# PMU.net
KiCad netlist of a schematic drawn in Altium Designer
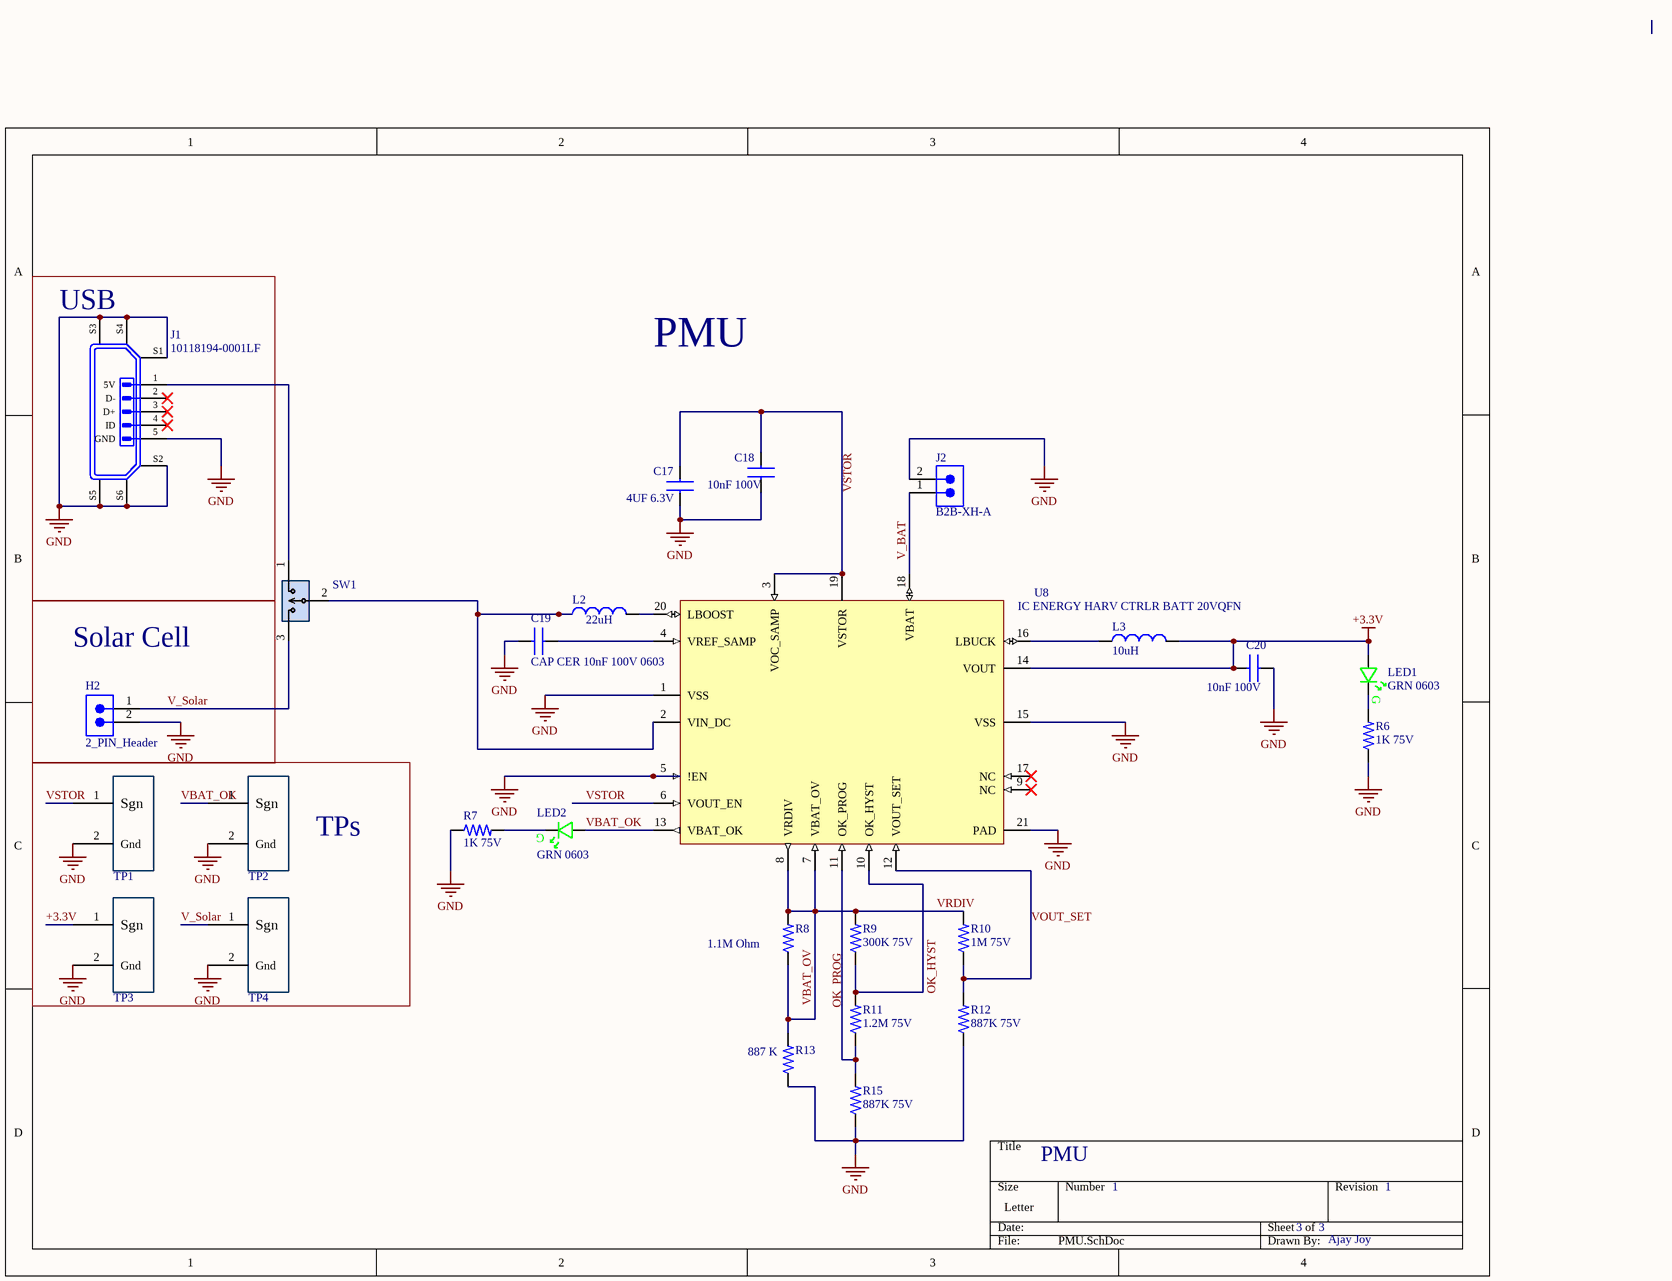
[diagram p0: PMU.SchDoc]

(export (version "E")
  (design (tool "Eeschema 10.0.6"))
  (components
    (comp (ref "C17")
      (value "4UF 6.3V")
      (footprint "CAP_0603_1MM")
      (fields
        (field (name "MANUFACTURER") "Samsung")
        (field (name "MANUFACTURER PART NUMBER") "CL10A105KQ8NNNC")
      )
      (libsource (lib "LPEDT_project_library") (part "CC_1uF_6.3v_0603"))
    )
    (comp (ref "C18")
      (value "10nF 100V")
      (footprint "CAP_0603_1MM")
      (fields
        (field (name "MANUFACTURER") "Murata")
        (field (name "MANUFACTURER PART NUMBER") "GCM188R72A103KA37D")
      )
      (libsource (lib "LPEDT_project_library") (part "GCM188R72A103KA37D"))
    )
    (comp (ref "C19")
      (value "CAP CER 10nF 100V 0603")
      (footprint "CAP_0603_1MM")
      (fields
        (field (name "MANUFACTURER") "Murata")
        (field (name "MANUFACTURER PART NUMBER") "GCM188R72A103KA37D")
      )
      (libsource (lib "LPEDT_project_library") (part "GCM188R72A103KA37D"))
    )
    (comp (ref "C20")
      (value "10nF 100V")
      (footprint "CAP_0603_1MM")
      (fields
        (field (name "MANUFACTURER") "Murata")
        (field (name "MANUFACTURER PART NUMBER") "GCM188R72A103KA37D")
      )
      (libsource (lib "LPEDT_project_library") (part "GCM188R72A103KA37D"))
    )
    (comp (ref "H2")
      (value "2_PIN_Header")
      (footprint "2-PIN_MALE_HEADER_01-IN")
      (description "CONN HEADER VERT 2POS 2.54MM")
      (fields
        (field (name "MANUFACTURER") "Sullins")
        (field (name "MANUFACTURER PART NUMBER") "PRPC002SAAN-RC")
      )
      (libsource (lib "Connectors") (part "PRPC002SAAN-RC"))
    )
    (comp (ref "J1")
      (value "micro-USB")
      (footprint "AMPHENOL_10118194-0001LF")
      (description "10118194-0001LF micro-USB paste-in-pad")
      (fields
        (field (name "MANUFACTURER") "FCI")
        (field (name "MANUFACTURER PART NUMBER") "10118194-0001LF")
        (field (name ".CREATOR") "Kailey Shara")
        (field (name ".SCHCHECKED") "KS")
        (field (name ".PCBCHECKED") "KS")
      )
      (libsource (lib "Connectors") (part "USB-Micro B"))
    )
    (comp (ref "J2")
      (value "B2B-XH-A")
      (footprint "JST_B2B-XH-A(LF)(SN)")
      (description "Board Connector, 2 Contact(s), 1 Row(s), Male, Straight, Solder Terminal,")
      (fields (field (name "MANUFACTURER") "JST"))
      (libsource (lib "LPEDT_project_library") (part "B2B-XH-A"))
    )
    (comp (ref "L2")
      (value "22uH")
      (footprint "IND_0603_1MM")
      (description "22 nH Unshielded Multilayer Inductor 300 mA 400mOhm Max 0603 (1608 Metric)")
      (fields
        (field (name "MANUFACTURER") "Tai Tech")
        (field (name "MANUFACTURER PART NUMBER") "HCI1608F-22NJ-M")
      )
      (libsource (lib "LPEDT_project_library") (part "IND_22nH_0.4OHM_300MA"))
    )
    (comp (ref "L3")
      (value "10uH")
      (footprint "IND_0603_1MM")
      (description "22 nH Unshielded Multilayer Inductor 300 mA 400mOhm Max 0603 (1608 Metric)")
      (fields
        (field (name "MANUFACTURER") "Tai Tech")
        (field (name "MANUFACTURER PART NUMBER") "HCI1608F-22NJ-M")
      )
      (libsource (lib "LPEDT_project_library") (part "IND_22nH_0.4OHM_300MA"))
    )
    (comp (ref "LED1")
      (value "GRN 0603")
      (footprint "LED_0603_GRN_WL-SMCW")
      (description "LED, 0603, GREEN, 430MCD, 520NM")
      (fields
        (field (name "MANUFACTURER") "Wurth Electronics")
        (field (name "MANUFACTURER PART NUMBER") "150060GS75000")
      )
      (libsource (lib "LPEDT_project_library") (part "150060GS75000"))
    )
    (comp (ref "LED2")
      (value "GRN 0603")
      (footprint "LED_0603_GRN_WL-SMCW")
      (description "LED, 0603, GREEN, 430MCD, 520NM")
      (fields
        (field (name "MANUFACTURER") "Wurth Electronics")
        (field (name "MANUFACTURER PART NUMBER") "150060GS75000")
      )
      (libsource (lib "LPEDT_project_library") (part "150060GS75000"))
    )
    (comp (ref "R6")
      (value "1K 75V")
      (footprint "RES_0603_1608X06")
      (fields
        (field (name "MANUFACTURER") "Stackpole Electronics")
        (field (name "MANUFACTURER PART NUMBER") "RMCF0603FT4K70")
        (field (name "TOLERANCE") "1%")
      )
      (libsource (lib "LPEDT_project_library") (part "RMCF0603FT4K70"))
    )
    (comp (ref "R7")
      (value "1K 75V")
      (footprint "RES_0603_1608X06")
      (fields
        (field (name "MANUFACTURER") "Stackpole Electronics")
        (field (name "MANUFACTURER PART NUMBER") "RMCF0603FT4K70")
        (field (name "TOLERANCE") "1%")
      )
      (libsource (lib "LPEDT_project_library") (part "RMCF0603FT4K70"))
    )
    (comp (ref "R8")
      (value "1.1M Ohm")
      (footprint "RES_0603_1608X06")
      (fields
        (field (name "MANUFACTURER") "Stackpole Electronics")
        (field (name "MANUFACTURER PART NUMBER") "RMCF0603FT1M10")
        (field (name "TOLERANCE") "1%")
      )
      (libsource (lib "LPEDT_project_library") (part "RMCF0603FT1M10"))
    )
    (comp (ref "R9")
      (value "300K 75V")
      (footprint "RES_0603_1608X06")
      (fields
        (field (name "MANUFACTURER") "Stackpole Electronics")
        (field (name "MANUFACTURER PART NUMBER") "RMCF0603FT4K70")
        (field (name "TOLERANCE") "1%")
      )
      (libsource (lib "LPEDT_project_library") (part "RMCF0603FT4K70"))
    )
    (comp (ref "R10")
      (value "1M 75V")
      (footprint "RES_0603_1608X06")
      (fields
        (field (name "MANUFACTURER") "Stackpole Electronics")
        (field (name "MANUFACTURER PART NUMBER") "RMCF0603FT4K70")
        (field (name "TOLERANCE") "1%")
      )
      (libsource (lib "LPEDT_project_library") (part "RMCF0603FT4K70"))
    )
    (comp (ref "R11")
      (value "1.2M 75V")
      (footprint "RES_0603_1608X06")
      (fields
        (field (name "MANUFACTURER") "Stackpole Electronics")
        (field (name "MANUFACTURER PART NUMBER") "RMCF0603FT4K70")
        (field (name "TOLERANCE") "1%")
      )
      (libsource (lib "LPEDT_project_library") (part "RMCF0603FT4K70"))
    )
    (comp (ref "R12")
      (value "887K 75V")
      (footprint "RES_0603_1608X06")
      (fields
        (field (name "MANUFACTURER") "Stackpole Electronics")
        (field (name "MANUFACTURER PART NUMBER") "RMCF0603FT4K70")
        (field (name "TOLERANCE") "1%")
      )
      (libsource (lib "LPEDT_project_library") (part "RMCF0603FT4K70"))
    )
    (comp (ref "R13")
      (value "887 K")
      (footprint "RES_0603_1608X06")
      (fields
        (field (name "MANUFACTURER") "Stackpole Electronics")
        (field (name "MANUFACTURER PART NUMBER") "RMCF0603FT1M10")
        (field (name "TOLERANCE") "1%")
      )
      (libsource (lib "LPEDT_project_library") (part "RMCF0603FT1M10"))
    )
    (comp (ref "R15")
      (value "887K 75V")
      (footprint "RES_0603_1608X06")
      (fields
        (field (name "MANUFACTURER") "Stackpole Electronics")
        (field (name "MANUFACTURER PART NUMBER") "RMCF0603FT4K70")
        (field (name "TOLERANCE") "1%")
      )
      (libsource (lib "LPEDT_project_library") (part "RMCF0603FT4K70"))
    )
    (comp (ref "SW1")
      (value "PREC003SAAN-RC")
      (footprint "3_PIN_100mil")
      (description "Connector Header Through Hole 3 position 0.100\" (2.54mm)")
      (fields (field (name "LCSC PART#") "C49257"))
      (libsource (lib "ECEN5730Lib_2023_05_DS") (part "SW_3Pin_100mil_Switch"))
    )
    (comp (ref "TP1")
      (value "TP_Active_Probe")
      (footprint "Active_Probe")
      (description "Active Probe Test Point footprint")
      (libsource (lib "ECEN5730Lib_Manual_2022_07LibPkg_1") (part "TP_Active_Probe"))
    )
    (comp (ref "TP2")
      (value "TP_Active_Probe")
      (footprint "Active_Probe")
      (description "Active Probe Test Point footprint")
      (libsource (lib "ECEN5730Lib_Manual_2022_07LibPkg_1") (part "TP_Active_Probe"))
    )
    (comp (ref "TP3")
      (value "TP_Active_Probe")
      (footprint "Active_Probe")
      (description "Active Probe Test Point footprint")
      (libsource (lib "ECEN5730Lib_Manual_2022_07LibPkg_1") (part "TP_Active_Probe"))
    )
    (comp (ref "TP4")
      (value "TP_Active_Probe")
      (footprint "Active_Probe")
      (description "Active Probe Test Point footprint")
      (libsource (lib "ECEN5730Lib_Manual_2022_07LibPkg_1") (part "TP_Active_Probe"))
    )
    (comp (ref "U8")
      (value "IC ENERGY HARV CTRLR BATT 20VQFN")
      (footprint "20-VQFN_3.3x3.3_BQ25570RGRR")
      (description "Power Supply Support Circuit, Adjustable, 1 Channel, PQCC20")
      (fields
        (field (name "MANUFACTURER") "Texas Instruments")
        (field (name "MANUFACTURER PART NUMBER") "BQ25570RGRR")
      )
      (libsource (lib "LPEDT_project_library") (part "BQ25570RGRR"))
    )
  )
  (nets
    (net (code "1") (name "+3.3V") (class "Default")
      (node (ref "C20") (pin "1") (pinfunction "1_1") (pintype "passive"))
      (node (ref "L3") (pin "2") (pinfunction "2_2") (pintype "passive"))
      (node (ref "LED1") (pin "A") (pinfunction "A_A") (pintype "passive"))
      (node (ref "TP3") (pin "1") (pinfunction "Sgn_1") (pintype "passive"))
      (node (ref "U8") (pin "14") (pinfunction "VOUT_14") (pintype "power_in"))
    )
    (net (code "2") (name "/OK_HYST") (class "Default")
      (node (ref "R11") (pin "2") (pinfunction "2_2") (pintype "passive"))
      (node (ref "R9") (pin "1") (pinfunction "1_1") (pintype "passive"))
      (node (ref "U8") (pin "10") (pinfunction "OK_HYST_10") (pintype "input"))
    )
    (net (code "4") (name "/VBAT_OK") (class "Default")
      (node (ref "LED2") (pin "A") (pinfunction "A_A") (pintype "passive"))
      (node (ref "TP2") (pin "1") (pinfunction "Sgn_1") (pintype "passive"))
      (node (ref "U8") (pin "13") (pinfunction "VBAT_OK_13") (pintype "output"))
    )
    (net (code "5") (name "/VBAT_OV") (class "Default")
      (node (ref "R10") (pin "2") (pinfunction "2_2") (pintype "passive"))
      (node (ref "R13") (pin "2") (pinfunction "2_2") (pintype "passive"))
      (node (ref "R8") (pin "1") (pinfunction "1_1") (pintype "passive"))
      (node (ref "R8") (pin "2") (pinfunction "2_2") (pintype "passive"))
      (node (ref "R9") (pin "2") (pinfunction "2_2") (pintype "passive"))
      (node (ref "U8") (pin "7") (pinfunction "VBAT_OV_7") (pintype "input"))
      (node (ref "U8") (pin "8") (pinfunction "VRDIV_8") (pintype "output"))
    )
    (net (code "6") (name "/VOUT_SET") (class "Default")
      (node (ref "R10") (pin "1") (pinfunction "1_1") (pintype "passive"))
      (node (ref "R12") (pin "2") (pinfunction "2_2") (pintype "passive"))
      (node (ref "U8") (pin "12") (pinfunction "VOUT_SET_12") (pintype "input"))
    )
    (net (code "7") (name "/VSTOR") (class "Default")
      (node (ref "TP1") (pin "1") (pinfunction "Sgn_1") (pintype "passive"))
      (node (ref "U8") (pin "6") (pinfunction "VOUT_EN_6") (pintype "input"))
    )
    (net (code "8") (name "/V_BAT") (class "Default")
      (node (ref "J2") (pin "1") (pinfunction "1_1") (pintype "passive"))
      (node (ref "U8") (pin "18") (pinfunction "VBAT_18") (pintype "bidirectional"))
    )
    (net (code "9") (name "/V_Solar") (class "Default")
      (node (ref "H2") (pin "1") (pinfunction "1_1") (pintype "passive"))
      (node (ref "SW1") (pin "3") (pinfunction "3_3") (pintype "passive"))
      (node (ref "TP4") (pin "1") (pinfunction "Sgn_1") (pintype "passive"))
    )
    (net (code "10") (name "GND") (class "Default")
      (node (ref "C17") (pin "2") (pinfunction "2_2") (pintype "passive"))
      (node (ref "C18") (pin "2") (pinfunction "2_2") (pintype "passive"))
      (node (ref "C19") (pin "1") (pinfunction "1_1") (pintype "passive"))
      (node (ref "C20") (pin "2") (pinfunction "2_2") (pintype "passive"))
      (node (ref "H2") (pin "2") (pinfunction "2_2") (pintype "passive"))
      (node (ref "J1") (pin "5") (pinfunction "GND_5") (pintype "power_in"))
      (node (ref "J1") (pin "S1") (pinfunction "GND_S1") (pintype "power_in"))
      (node (ref "J1") (pin "S2") (pinfunction "GND_S2") (pintype "power_in"))
      (node (ref "J1") (pin "S3") (pinfunction "GND_S3") (pintype "power_in"))
      (node (ref "J1") (pin "S4") (pinfunction "GND_S4") (pintype "power_in"))
      (node (ref "J1") (pin "S5") (pinfunction "GND_S5") (pintype "power_in"))
      (node (ref "J1") (pin "S6") (pinfunction "GND_S6") (pintype "power_in"))
      (node (ref "J2") (pin "2") (pinfunction "2_2") (pintype "passive"))
      (node (ref "R12") (pin "1") (pinfunction "1_1") (pintype "passive"))
      (node (ref "R13") (pin "1") (pinfunction "1_1") (pintype "passive"))
      (node (ref "R15") (pin "1") (pinfunction "1_1") (pintype "passive"))
      (node (ref "R6") (pin "1") (pinfunction "1_1") (pintype "passive"))
      (node (ref "R7") (pin "1") (pinfunction "1_1") (pintype "passive"))
      (node (ref "TP1") (pin "2") (pinfunction "Gnd_2") (pintype "passive"))
      (node (ref "TP2") (pin "2") (pinfunction "Gnd_2") (pintype "passive"))
      (node (ref "TP3") (pin "2") (pinfunction "Gnd_2") (pintype "passive"))
      (node (ref "TP4") (pin "2") (pinfunction "Gnd_2") (pintype "passive"))
      (node (ref "U8") (pin "1") (pinfunction "VSS_1") (pintype "power_in"))
      (node (ref "U8") (pin "15") (pinfunction "VSS_15") (pintype "power_in"))
      (node (ref "U8") (pin "21") (pinfunction "PAD_21") (pintype "passive"))
      (node (ref "U8") (pin "5") (pinfunction "!EN_5") (pintype "input"))
    )
    (net (code "11") (name "Net-(J1-5V)") (class "Default")
      (node (ref "J1") (pin "1") (pinfunction "5V_1") (pintype "power_in"))
      (node (ref "SW1") (pin "1") (pinfunction "1_1") (pintype "passive"))
    )
    (net (code "12") (name "Net-(LED1-PadC)") (class "Default")
      (node (ref "LED1") (pin "C") (pinfunction "C_C") (pintype "passive"))
      (node (ref "R6") (pin "2") (pinfunction "2_2") (pintype "passive"))
    )
    (net (code "13") (name "Net-(LED2-PadC)") (class "Default")
      (node (ref "LED2") (pin "C") (pinfunction "C_C") (pintype "passive"))
      (node (ref "R7") (pin "2") (pinfunction "2_2") (pintype "passive"))
    )
    (net (code "14") (name "Net-(U8-LBOOST)") (class "Default")
      (node (ref "L2") (pin "2") (pinfunction "2_2") (pintype "passive"))
      (node (ref "U8") (pin "20") (pinfunction "LBOOST_20") (pintype "bidirectional"))
    )
    (net (code "15") (name "Net-(U8-LBUCK)") (class "Default")
      (node (ref "L3") (pin "1") (pinfunction "1_1") (pintype "passive"))
      (node (ref "U8") (pin "16") (pinfunction "LBUCK_16") (pintype "bidirectional"))
    )
    (net (code "16") (name "Net-(U8-OK_PROG)") (class "Default")
      (node (ref "R11") (pin "1") (pinfunction "1_1") (pintype "passive"))
      (node (ref "R15") (pin "2") (pinfunction "2_2") (pintype "passive"))
      (node (ref "U8") (pin "11") (pinfunction "OK_PROG_11") (pintype "input"))
    )
    (net (code "17") (name "Net-(U8-VIN_DC)") (class "Default")
      (node (ref "L2") (pin "1") (pinfunction "1_1") (pintype "passive"))
      (node (ref "SW1") (pin "2") (pinfunction "2_2") (pintype "passive"))
      (node (ref "U8") (pin "2") (pinfunction "VIN_DC_2") (pintype "power_in"))
    )
    (net (code "18") (name "Net-(U8-VOC_SAMP)") (class "Default")
      (node (ref "C17") (pin "1") (pinfunction "1_1") (pintype "passive"))
      (node (ref "C18") (pin "1") (pinfunction "1_1") (pintype "passive"))
      (node (ref "U8") (pin "19") (pinfunction "VSTOR_19") (pintype "power_in"))
      (node (ref "U8") (pin "3") (pinfunction "VOC_SAMP_3") (pintype "input"))
    )
    (net (code "19") (name "Net-(U8-VREF_SAMP)") (class "Default")
      (node (ref "C19") (pin "2") (pinfunction "2_2") (pintype "passive"))
      (node (ref "U8") (pin "4") (pinfunction "VREF_SAMP_4") (pintype "input"))
    )
    (net (code "20") (name "unconnected-(J1-D+-Pad3)") (class "Default")
      (node (ref "J1") (pin "3") (pinfunction "D+_3") (pintype "passive+no_connect"))
    )
    (net (code "21") (name "unconnected-(J1-D--Pad2)") (class "Default")
      (node (ref "J1") (pin "2") (pinfunction "D-_2") (pintype "passive+no_connect"))
    )
    (net (code "22") (name "unconnected-(J1-ID-Pad4)") (class "Default")
      (node (ref "J1") (pin "4") (pinfunction "ID_4") (pintype "passive+no_connect"))
    )
    (net (code "23") (name "unconnected-(U8-NC-Pad9)") (class "Default")
      (node (ref "U8") (pin "9") (pinfunction "NC_9") (pintype "input+no_connect"))
    )
    (net (code "24") (name "unconnected-(U8-NC-Pad17)") (class "Default")
      (node (ref "U8") (pin "17") (pinfunction "NC_17") (pintype "input+no_connect"))
    )
  )
)
